# LED_Monitor_2.net
KiCad netlist of a schematic drawn in Altium Designer
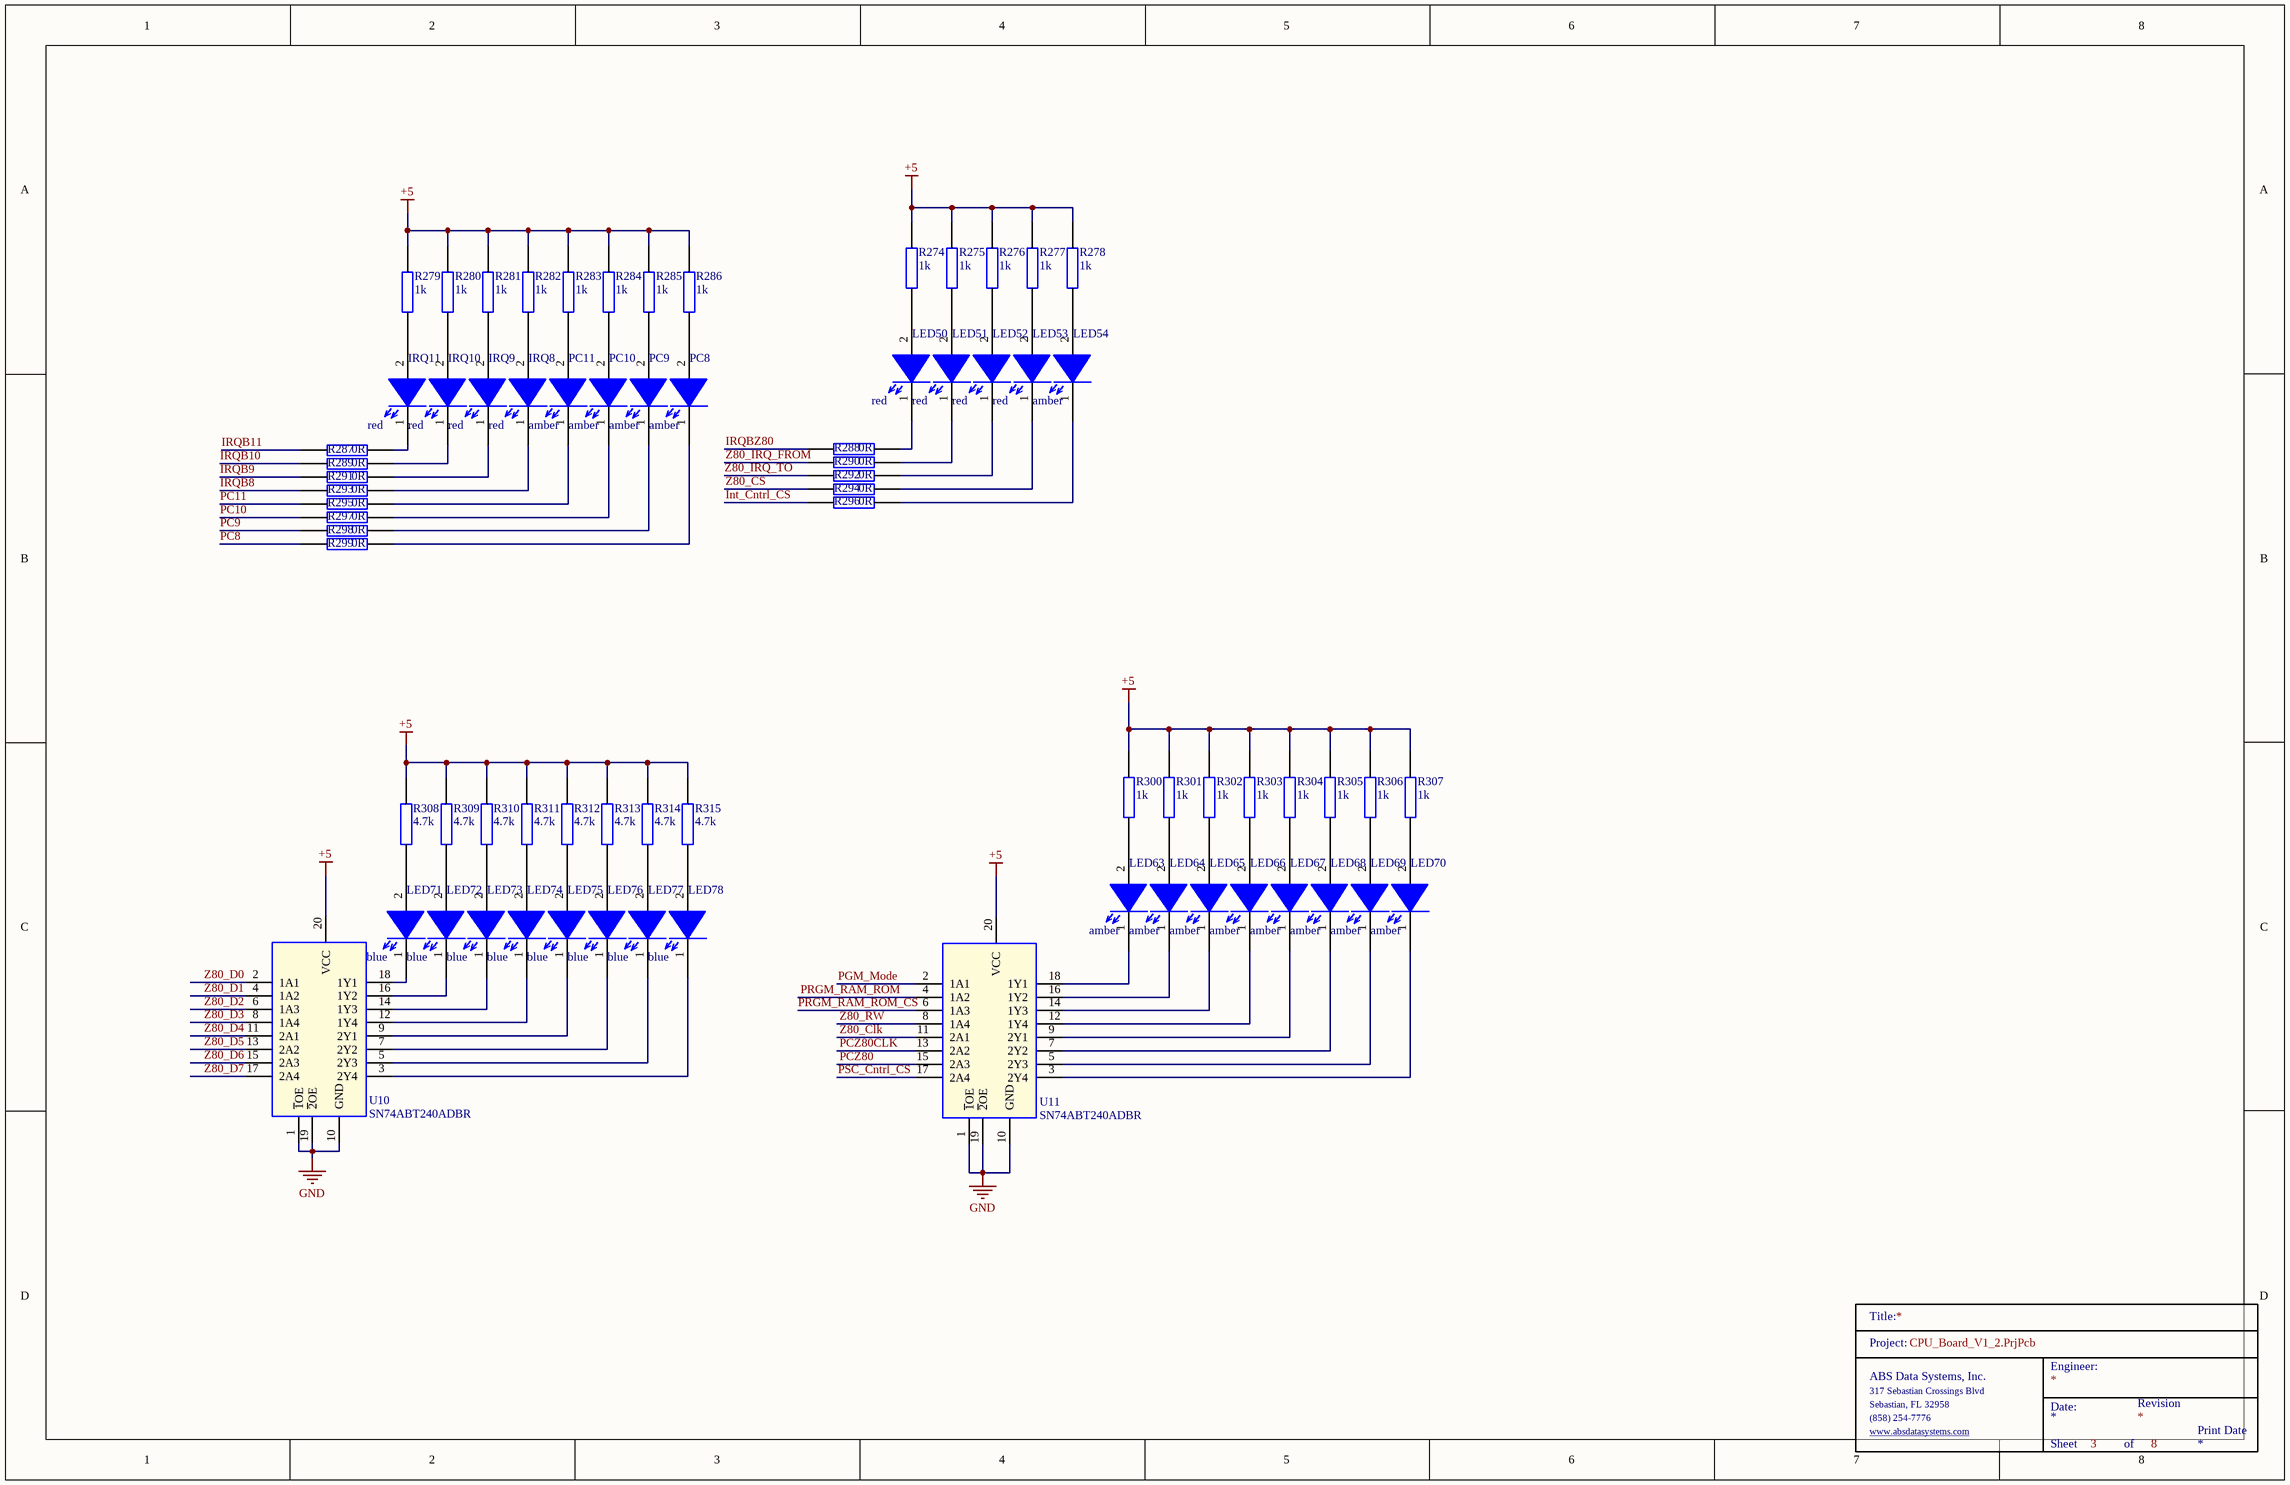
[diagram p0: LED_Monitor_2.SchDoc]

(export (version "E")
  (design (tool "Eeschema 10.0.6"))
  (components
    (comp (ref "IRQ8")
      (value "red")
      (footprint "0603_Diode")
      (description "Wurth Elektronik 0603 red")
      (fields
        (field (name "MANUFACTURER") "Wurth Electronics")
        (field (name "MANUFACTURER PART NUMBER") "150060GS75000")
      )
      (libsource (lib "Misc") (part "150060RS75000"))
    )
    (comp (ref "IRQ9")
      (value "red")
      (footprint "0603_Diode")
      (description "Wurth Elektronik 0603 red")
      (fields
        (field (name "MANUFACTURER") "Wurth Electronics")
        (field (name "MANUFACTURER PART NUMBER") "150060GS75000")
      )
      (libsource (lib "Misc") (part "150060RS75000"))
    )
    (comp (ref "IRQ10")
      (value "red")
      (footprint "0603_Diode")
      (description "Wurth Elektronik 0603 red")
      (fields
        (field (name "MANUFACTURER") "Wurth Electronics")
        (field (name "MANUFACTURER PART NUMBER") "150060GS75000")
      )
      (libsource (lib "Misc") (part "150060RS75000"))
    )
    (comp (ref "IRQ11")
      (value "red")
      (footprint "0603_Diode")
      (description "Wurth Elektronik 0603 red")
      (fields
        (field (name "MANUFACTURER") "Wurth Electronics")
        (field (name "MANUFACTURER PART NUMBER") "150060GS75000")
      )
      (libsource (lib "Misc") (part "150060RS75000"))
    )
    (comp (ref "LED50")
      (value "red")
      (footprint "0603_Diode")
      (description "Wurth Elektronik 0603 red")
      (fields
        (field (name "MANUFACTURER") "Wurth Electronics")
        (field (name "MANUFACTURER PART NUMBER") "150060GS75000")
      )
      (libsource (lib "Misc") (part "150060RS75000"))
    )
    (comp (ref "LED51")
      (value "red")
      (footprint "0603_Diode")
      (description "Wurth Elektronik 0603 red")
      (fields
        (field (name "MANUFACTURER") "Wurth Electronics")
        (field (name "MANUFACTURER PART NUMBER") "150060GS75000")
      )
      (libsource (lib "Misc") (part "150060RS75000"))
    )
    (comp (ref "LED52")
      (value "red")
      (footprint "0603_Diode")
      (description "Wurth Elektronik 0603 red")
      (fields
        (field (name "MANUFACTURER") "Wurth Electronics")
        (field (name "MANUFACTURER PART NUMBER") "150060GS75000")
      )
      (libsource (lib "Misc") (part "150060RS75000"))
    )
    (comp (ref "LED53")
      (value "red")
      (footprint "0603_Diode")
      (description "Wurth Elektronik 0603 red")
      (fields
        (field (name "MANUFACTURER") "Wurth Electronics")
        (field (name "MANUFACTURER PART NUMBER") "150060GS75000")
      )
      (libsource (lib "Misc") (part "150060RS75000"))
    )
    (comp (ref "LED54")
      (value "amber")
      (footprint "0603_Diode")
      (description "Wurth Elektronik 0603 amber")
      (fields
        (field (name "MANUFACTURER") "Wurth Electronics")
        (field (name "MANUFACTURER PART NUMBER") "150060GS75000")
      )
      (libsource (lib "Misc") (part "150060AS75000"))
    )
    (comp (ref "LED63")
      (value "amber")
      (footprint "0603_Diode")
      (description "Wurth Elektronik 0603 amber")
      (fields
        (field (name "MANUFACTURER") "Wurth Electronics")
        (field (name "MANUFACTURER PART NUMBER") "150060GS75000")
      )
      (libsource (lib "Misc") (part "150060AS75000"))
    )
    (comp (ref "LED64")
      (value "amber")
      (footprint "0603_Diode")
      (description "Wurth Elektronik 0603 amber")
      (fields
        (field (name "MANUFACTURER") "Wurth Electronics")
        (field (name "MANUFACTURER PART NUMBER") "150060GS75000")
      )
      (libsource (lib "Misc") (part "150060AS75000"))
    )
    (comp (ref "LED65")
      (value "amber")
      (footprint "0603_Diode")
      (description "Wurth Elektronik 0603 amber")
      (fields
        (field (name "MANUFACTURER") "Wurth Electronics")
        (field (name "MANUFACTURER PART NUMBER") "150060GS75000")
      )
      (libsource (lib "Misc") (part "150060AS75000"))
    )
    (comp (ref "LED66")
      (value "amber")
      (footprint "0603_Diode")
      (description "Wurth Elektronik 0603 amber")
      (fields
        (field (name "MANUFACTURER") "Wurth Electronics")
        (field (name "MANUFACTURER PART NUMBER") "150060GS75000")
      )
      (libsource (lib "Misc") (part "150060AS75000"))
    )
    (comp (ref "LED67")
      (value "amber")
      (footprint "0603_Diode")
      (description "Wurth Elektronik 0603 amber")
      (fields
        (field (name "MANUFACTURER") "Wurth Electronics")
        (field (name "MANUFACTURER PART NUMBER") "150060GS75000")
      )
      (libsource (lib "Misc") (part "150060AS75000"))
    )
    (comp (ref "LED68")
      (value "amber")
      (footprint "0603_Diode")
      (description "Wurth Elektronik 0603 amber")
      (fields
        (field (name "MANUFACTURER") "Wurth Electronics")
        (field (name "MANUFACTURER PART NUMBER") "150060GS75000")
      )
      (libsource (lib "Misc") (part "150060AS75000"))
    )
    (comp (ref "LED69")
      (value "amber")
      (footprint "0603_Diode")
      (description "Wurth Elektronik 0603 amber")
      (fields
        (field (name "MANUFACTURER") "Wurth Electronics")
        (field (name "MANUFACTURER PART NUMBER") "150060GS75000")
      )
      (libsource (lib "Misc") (part "150060AS75000"))
    )
    (comp (ref "LED70")
      (value "amber")
      (footprint "0603_Diode")
      (description "Wurth Elektronik 0603 amber")
      (fields
        (field (name "MANUFACTURER") "Wurth Electronics")
        (field (name "MANUFACTURER PART NUMBER") "150060GS75000")
      )
      (libsource (lib "Misc") (part "150060AS75000"))
    )
    (comp (ref "LED71")
      (value "blue")
      (footprint "0603_Diode")
      (description "Wurth Elektronik 0603 blue")
      (fields
        (field (name "MANUFACTURER") "Wurth Electronics")
        (field (name "MANUFACTURER PART NUMBER") "150060GS75000")
      )
      (libsource (lib "Misc") (part "150060BS75000"))
    )
    (comp (ref "LED72")
      (value "blue")
      (footprint "0603_Diode")
      (description "Wurth Elektronik 0603 blue")
      (fields
        (field (name "MANUFACTURER") "Wurth Electronics")
        (field (name "MANUFACTURER PART NUMBER") "150060GS75000")
      )
      (libsource (lib "Misc") (part "150060BS75000"))
    )
    (comp (ref "LED73")
      (value "blue")
      (footprint "0603_Diode")
      (description "Wurth Elektronik 0603 blue")
      (fields
        (field (name "MANUFACTURER") "Wurth Electronics")
        (field (name "MANUFACTURER PART NUMBER") "150060GS75000")
      )
      (libsource (lib "Misc") (part "150060BS75000"))
    )
    (comp (ref "LED74")
      (value "blue")
      (footprint "0603_Diode")
      (description "Wurth Elektronik 0603 blue")
      (fields
        (field (name "MANUFACTURER") "Wurth Electronics")
        (field (name "MANUFACTURER PART NUMBER") "150060GS75000")
      )
      (libsource (lib "Misc") (part "150060BS75000"))
    )
    (comp (ref "LED75")
      (value "blue")
      (footprint "0603_Diode")
      (description "Wurth Elektronik 0603 blue")
      (fields
        (field (name "MANUFACTURER") "Wurth Electronics")
        (field (name "MANUFACTURER PART NUMBER") "150060GS75000")
      )
      (libsource (lib "Misc") (part "150060BS75000"))
    )
    (comp (ref "LED76")
      (value "blue")
      (footprint "0603_Diode")
      (description "Wurth Elektronik 0603 blue")
      (fields
        (field (name "MANUFACTURER") "Wurth Electronics")
        (field (name "MANUFACTURER PART NUMBER") "150060GS75000")
      )
      (libsource (lib "Misc") (part "150060BS75000"))
    )
    (comp (ref "LED77")
      (value "blue")
      (footprint "0603_Diode")
      (description "Wurth Elektronik 0603 blue")
      (fields
        (field (name "MANUFACTURER") "Wurth Electronics")
        (field (name "MANUFACTURER PART NUMBER") "150060GS75000")
      )
      (libsource (lib "Misc") (part "150060BS75000"))
    )
    (comp (ref "LED78")
      (value "blue")
      (footprint "0603_Diode")
      (description "Wurth Elektronik 0603 blue")
      (fields
        (field (name "MANUFACTURER") "Wurth Electronics")
        (field (name "MANUFACTURER PART NUMBER") "150060GS75000")
      )
      (libsource (lib "Misc") (part "150060BS75000"))
    )
    (comp (ref "PC8")
      (value "amber")
      (footprint "0603_Diode")
      (description "Wurth Elektronik 0603 amber")
      (fields
        (field (name "MANUFACTURER") "Wurth Electronics")
        (field (name "MANUFACTURER PART NUMBER") "150060GS75000")
      )
      (libsource (lib "Misc") (part "150060AS75000"))
    )
    (comp (ref "PC9")
      (value "amber")
      (footprint "0603_Diode")
      (description "Wurth Elektronik 0603 amber")
      (fields
        (field (name "MANUFACTURER") "Wurth Electronics")
        (field (name "MANUFACTURER PART NUMBER") "150060GS75000")
      )
      (libsource (lib "Misc") (part "150060AS75000"))
    )
    (comp (ref "PC10")
      (value "amber")
      (footprint "0603_Diode")
      (description "Wurth Elektronik 0603 amber")
      (fields
        (field (name "MANUFACTURER") "Wurth Electronics")
        (field (name "MANUFACTURER PART NUMBER") "150060GS75000")
      )
      (libsource (lib "Misc") (part "150060AS75000"))
    )
    (comp (ref "PC11")
      (value "amber")
      (footprint "0603_Diode")
      (description "Wurth Elektronik 0603 amber")
      (fields
        (field (name "MANUFACTURER") "Wurth Electronics")
        (field (name "MANUFACTURER PART NUMBER") "150060GS75000")
      )
      (libsource (lib "Misc") (part "150060AS75000"))
    )
    (comp (ref "R274")
      (value "1k")
      (footprint "0603")
      (description "YAGEO 0603 1k ohm")
      (fields
        (field (name "MOUSER PART NUMBER") "603-RC0603JR-070RL")
        (field (name "MANUFACTURER_PART_NUMBER") "RC0603JR-070RL")
      )
      (libsource (lib "Resistors") (part "AC0603FR-7W1KL_1"))
    )
    (comp (ref "R275")
      (value "1k")
      (footprint "0603")
      (description "YAGEO 0603 1k ohm")
      (fields
        (field (name "MOUSER PART NUMBER") "603-RC0603JR-070RL")
        (field (name "MANUFACTURER_PART_NUMBER") "RC0603JR-070RL")
      )
      (libsource (lib "Resistors") (part "AC0603FR-7W1KL_1"))
    )
    (comp (ref "R276")
      (value "1k")
      (footprint "0603")
      (description "YAGEO 0603 1k ohm")
      (fields
        (field (name "MOUSER PART NUMBER") "603-RC0603JR-070RL")
        (field (name "MANUFACTURER_PART_NUMBER") "RC0603JR-070RL")
      )
      (libsource (lib "Resistors") (part "AC0603FR-7W1KL_1"))
    )
    (comp (ref "R277")
      (value "1k")
      (footprint "0603")
      (description "YAGEO 0603 1k ohm")
      (fields
        (field (name "MOUSER PART NUMBER") "603-RC0603JR-070RL")
        (field (name "MANUFACTURER_PART_NUMBER") "RC0603JR-070RL")
      )
      (libsource (lib "Resistors") (part "AC0603FR-7W1KL_1"))
    )
    (comp (ref "R278")
      (value "1k")
      (footprint "0603")
      (description "YAGEO 0603 1k ohm")
      (fields
        (field (name "MOUSER PART NUMBER") "603-RC0603JR-070RL")
        (field (name "MANUFACTURER_PART_NUMBER") "RC0603JR-070RL")
      )
      (libsource (lib "Resistors") (part "AC0603FR-7W1KL_1"))
    )
    (comp (ref "R279")
      (value "1k")
      (footprint "0603")
      (description "YAGEO 0603 1k ohm")
      (fields
        (field (name "MOUSER PART NUMBER") "603-RC0603JR-070RL")
        (field (name "MANUFACTURER_PART_NUMBER") "RC0603JR-070RL")
      )
      (libsource (lib "Resistors") (part "AC0603FR-7W1KL_1"))
    )
    (comp (ref "R280")
      (value "1k")
      (footprint "0603")
      (description "YAGEO 0603 1k ohm")
      (fields
        (field (name "MOUSER PART NUMBER") "603-RC0603JR-070RL")
        (field (name "MANUFACTURER_PART_NUMBER") "RC0603JR-070RL")
      )
      (libsource (lib "Resistors") (part "AC0603FR-7W1KL_1"))
    )
    (comp (ref "R281")
      (value "1k")
      (footprint "0603")
      (description "YAGEO 0603 1k ohm")
      (fields
        (field (name "MOUSER PART NUMBER") "603-RC0603JR-070RL")
        (field (name "MANUFACTURER_PART_NUMBER") "RC0603JR-070RL")
      )
      (libsource (lib "Resistors") (part "AC0603FR-7W1KL_1"))
    )
    (comp (ref "R282")
      (value "1k")
      (footprint "0603")
      (description "YAGEO 0603 1k ohm")
      (fields
        (field (name "MOUSER PART NUMBER") "603-RC0603JR-070RL")
        (field (name "MANUFACTURER_PART_NUMBER") "RC0603JR-070RL")
      )
      (libsource (lib "Resistors") (part "AC0603FR-7W1KL_1"))
    )
    (comp (ref "R283")
      (value "1k")
      (footprint "0603")
      (description "YAGEO 0603 1k ohm")
      (fields
        (field (name "MOUSER PART NUMBER") "603-RC0603JR-070RL")
        (field (name "MANUFACTURER_PART_NUMBER") "RC0603JR-070RL")
      )
      (libsource (lib "Resistors") (part "AC0603FR-7W1KL_1"))
    )
    (comp (ref "R284")
      (value "1k")
      (footprint "0603")
      (description "YAGEO 0603 1k ohm")
      (fields
        (field (name "MOUSER PART NUMBER") "603-RC0603JR-070RL")
        (field (name "MANUFACTURER_PART_NUMBER") "RC0603JR-070RL")
      )
      (libsource (lib "Resistors") (part "AC0603FR-7W1KL_1"))
    )
    (comp (ref "R285")
      (value "1k")
      (footprint "0603")
      (description "YAGEO 0603 1k ohm")
      (fields
        (field (name "MOUSER PART NUMBER") "603-RC0603JR-070RL")
        (field (name "MANUFACTURER_PART_NUMBER") "RC0603JR-070RL")
      )
      (libsource (lib "Resistors") (part "AC0603FR-7W1KL_1"))
    )
    (comp (ref "R286")
      (value "1k")
      (footprint "0603")
      (description "YAGEO 0603 1k ohm")
      (fields
        (field (name "MOUSER PART NUMBER") "603-RC0603JR-070RL")
        (field (name "MANUFACTURER_PART_NUMBER") "RC0603JR-070RL")
      )
      (libsource (lib "Resistors") (part "AC0603FR-7W1KL_1"))
    )
    (comp (ref "R287")
      (value "0R")
      (footprint "0603")
      (description "YAGEO 0603 0 ohm")
      (fields
        (field (name "MOUSER PART NUMBER") "603-RC0603JR-070RL")
        (field (name "MANUFACTURER_PART_NUMBER") "RC0603JR-070RL")
      )
      (libsource (lib "Resistors") (part "RC0603JR-070RL"))
    )
    (comp (ref "R288")
      (value "0R")
      (footprint "0603")
      (description "YAGEO 0603 0 ohm")
      (fields
        (field (name "MOUSER PART NUMBER") "603-RC0603JR-070RL")
        (field (name "MANUFACTURER_PART_NUMBER") "RC0603JR-070RL")
      )
      (libsource (lib "Resistors") (part "RC0603JR-070RL"))
    )
    (comp (ref "R289")
      (value "0R")
      (footprint "0603")
      (description "YAGEO 0603 0 ohm")
      (fields
        (field (name "MOUSER PART NUMBER") "603-RC0603JR-070RL")
        (field (name "MANUFACTURER_PART_NUMBER") "RC0603JR-070RL")
      )
      (libsource (lib "Resistors") (part "RC0603JR-070RL"))
    )
    (comp (ref "R290")
      (value "0R")
      (footprint "0603")
      (description "YAGEO 0603 0 ohm")
      (fields
        (field (name "MOUSER PART NUMBER") "603-RC0603JR-070RL")
        (field (name "MANUFACTURER_PART_NUMBER") "RC0603JR-070RL")
      )
      (libsource (lib "Resistors") (part "RC0603JR-070RL"))
    )
    (comp (ref "R291")
      (value "0R")
      (footprint "0603")
      (description "YAGEO 0603 0 ohm")
      (fields
        (field (name "MOUSER PART NUMBER") "603-RC0603JR-070RL")
        (field (name "MANUFACTURER_PART_NUMBER") "RC0603JR-070RL")
      )
      (libsource (lib "Resistors") (part "RC0603JR-070RL"))
    )
    (comp (ref "R292")
      (value "0R")
      (footprint "0603")
      (description "YAGEO 0603 0 ohm")
      (fields
        (field (name "MOUSER PART NUMBER") "603-RC0603JR-070RL")
        (field (name "MANUFACTURER_PART_NUMBER") "RC0603JR-070RL")
      )
      (libsource (lib "Resistors") (part "RC0603JR-070RL"))
    )
    (comp (ref "R293")
      (value "0R")
      (footprint "0603")
      (description "YAGEO 0603 0 ohm")
      (fields
        (field (name "MOUSER PART NUMBER") "603-RC0603JR-070RL")
        (field (name "MANUFACTURER_PART_NUMBER") "RC0603JR-070RL")
      )
      (libsource (lib "Resistors") (part "RC0603JR-070RL"))
    )
    (comp (ref "R294")
      (value "0R")
      (footprint "0603")
      (description "YAGEO 0603 0 ohm")
      (fields
        (field (name "MOUSER PART NUMBER") "603-RC0603JR-070RL")
        (field (name "MANUFACTURER_PART_NUMBER") "RC0603JR-070RL")
      )
      (libsource (lib "Resistors") (part "RC0603JR-070RL"))
    )
    (comp (ref "R295")
      (value "0R")
      (footprint "0603")
      (description "YAGEO 0603 0 ohm")
      (fields
        (field (name "MOUSER PART NUMBER") "603-RC0603JR-070RL")
        (field (name "MANUFACTURER_PART_NUMBER") "RC0603JR-070RL")
      )
      (libsource (lib "Resistors") (part "RC0603JR-070RL"))
    )
    (comp (ref "R296")
      (value "0R")
      (footprint "0603")
      (description "YAGEO 0603 0 ohm")
      (fields
        (field (name "MOUSER PART NUMBER") "603-RC0603JR-070RL")
        (field (name "MANUFACTURER_PART_NUMBER") "RC0603JR-070RL")
      )
      (libsource (lib "Resistors") (part "RC0603JR-070RL"))
    )
    (comp (ref "R297")
      (value "0R")
      (footprint "0603")
      (description "YAGEO 0603 0 ohm")
      (fields
        (field (name "MOUSER PART NUMBER") "603-RC0603JR-070RL")
        (field (name "MANUFACTURER_PART_NUMBER") "RC0603JR-070RL")
      )
      (libsource (lib "Resistors") (part "RC0603JR-070RL"))
    )
    (comp (ref "R298")
      (value "0R")
      (footprint "0603")
      (description "YAGEO 0603 0 ohm")
      (fields
        (field (name "MOUSER PART NUMBER") "603-RC0603JR-070RL")
        (field (name "MANUFACTURER_PART_NUMBER") "RC0603JR-070RL")
      )
      (libsource (lib "Resistors") (part "RC0603JR-070RL"))
    )
    (comp (ref "R299")
      (value "0R")
      (footprint "0603")
      (description "YAGEO 0603 0 ohm")
      (fields
        (field (name "MOUSER PART NUMBER") "603-RC0603JR-070RL")
        (field (name "MANUFACTURER_PART_NUMBER") "RC0603JR-070RL")
      )
      (libsource (lib "Resistors") (part "RC0603JR-070RL"))
    )
    (comp (ref "R300")
      (value "1k")
      (footprint "0603")
      (description "YAGEO 0603 1k ohm")
      (fields
        (field (name "MOUSER PART NUMBER") "603-RC0603JR-070RL")
        (field (name "MANUFACTURER_PART_NUMBER") "RC0603JR-070RL")
      )
      (libsource (lib "Resistors") (part "AC0603FR-7W1KL_1"))
    )
    (comp (ref "R301")
      (value "1k")
      (footprint "0603")
      (description "YAGEO 0603 1k ohm")
      (fields
        (field (name "MOUSER PART NUMBER") "603-RC0603JR-070RL")
        (field (name "MANUFACTURER_PART_NUMBER") "RC0603JR-070RL")
      )
      (libsource (lib "Resistors") (part "AC0603FR-7W1KL_1"))
    )
    (comp (ref "R302")
      (value "1k")
      (footprint "0603")
      (description "YAGEO 0603 1k ohm")
      (fields
        (field (name "MOUSER PART NUMBER") "603-RC0603JR-070RL")
        (field (name "MANUFACTURER_PART_NUMBER") "RC0603JR-070RL")
      )
      (libsource (lib "Resistors") (part "AC0603FR-7W1KL_1"))
    )
    (comp (ref "R303")
      (value "1k")
      (footprint "0603")
      (description "YAGEO 0603 1k ohm")
      (fields
        (field (name "MOUSER PART NUMBER") "603-RC0603JR-070RL")
        (field (name "MANUFACTURER_PART_NUMBER") "RC0603JR-070RL")
      )
      (libsource (lib "Resistors") (part "AC0603FR-7W1KL_1"))
    )
    (comp (ref "R304")
      (value "1k")
      (footprint "0603")
      (description "YAGEO 0603 1k ohm")
      (fields
        (field (name "MOUSER PART NUMBER") "603-RC0603JR-070RL")
        (field (name "MANUFACTURER_PART_NUMBER") "RC0603JR-070RL")
      )
      (libsource (lib "Resistors") (part "AC0603FR-7W1KL_1"))
    )
    (comp (ref "R305")
      (value "1k")
      (footprint "0603")
      (description "YAGEO 0603 1k ohm")
      (fields
        (field (name "MOUSER PART NUMBER") "603-RC0603JR-070RL")
        (field (name "MANUFACTURER_PART_NUMBER") "RC0603JR-070RL")
      )
      (libsource (lib "Resistors") (part "AC0603FR-7W1KL_1"))
    )
    (comp (ref "R306")
      (value "1k")
      (footprint "0603")
      (description "YAGEO 0603 1k ohm")
      (fields
        (field (name "MOUSER PART NUMBER") "603-RC0603JR-070RL")
        (field (name "MANUFACTURER_PART_NUMBER") "RC0603JR-070RL")
      )
      (libsource (lib "Resistors") (part "AC0603FR-7W1KL_1"))
    )
    (comp (ref "R307")
      (value "1k")
      (footprint "0603")
      (description "YAGEO 0603 1k ohm")
      (fields
        (field (name "MOUSER PART NUMBER") "603-RC0603JR-070RL")
        (field (name "MANUFACTURER_PART_NUMBER") "RC0603JR-070RL")
      )
      (libsource (lib "Resistors") (part "AC0603FR-7W1KL_1"))
    )
    (comp (ref "R308")
      (value "4.7k")
      (footprint "0603")
      (description "YAGEO 0603 4.7k")
      (fields
        (field (name "MOUSER PART NUMBER") "603-RC0603JR-070RL")
        (field (name "MANUFACTURER_PART_NUMBER") "RC0603JR-070RL")
      )
      (libsource (lib "Resistors") (part "RC0603FR-104K7L"))
    )
    (comp (ref "R309")
      (value "4.7k")
      (footprint "0603")
      (description "YAGEO 0603 4.7k")
      (fields
        (field (name "MOUSER PART NUMBER") "603-RC0603JR-070RL")
        (field (name "MANUFACTURER_PART_NUMBER") "RC0603JR-070RL")
      )
      (libsource (lib "Resistors") (part "RC0603FR-104K7L"))
    )
    (comp (ref "R310")
      (value "4.7k")
      (footprint "0603")
      (description "YAGEO 0603 4.7k")
      (fields
        (field (name "MOUSER PART NUMBER") "603-RC0603JR-070RL")
        (field (name "MANUFACTURER_PART_NUMBER") "RC0603JR-070RL")
      )
      (libsource (lib "Resistors") (part "RC0603FR-104K7L"))
    )
    (comp (ref "R311")
      (value "4.7k")
      (footprint "0603")
      (description "YAGEO 0603 4.7k")
      (fields
        (field (name "MOUSER PART NUMBER") "603-RC0603JR-070RL")
        (field (name "MANUFACTURER_PART_NUMBER") "RC0603JR-070RL")
      )
      (libsource (lib "Resistors") (part "RC0603FR-104K7L"))
    )
    (comp (ref "R312")
      (value "4.7k")
      (footprint "0603")
      (description "YAGEO 0603 4.7k")
      (fields
        (field (name "MOUSER PART NUMBER") "603-RC0603JR-070RL")
        (field (name "MANUFACTURER_PART_NUMBER") "RC0603JR-070RL")
      )
      (libsource (lib "Resistors") (part "RC0603FR-104K7L"))
    )
    (comp (ref "R313")
      (value "4.7k")
      (footprint "0603")
      (description "YAGEO 0603 4.7k")
      (fields
        (field (name "MOUSER PART NUMBER") "603-RC0603JR-070RL")
        (field (name "MANUFACTURER_PART_NUMBER") "RC0603JR-070RL")
      )
      (libsource (lib "Resistors") (part "RC0603FR-104K7L"))
    )
    (comp (ref "R314")
      (value "4.7k")
      (footprint "0603")
      (description "YAGEO 0603 4.7k")
      (fields
        (field (name "MOUSER PART NUMBER") "603-RC0603JR-070RL")
        (field (name "MANUFACTURER_PART_NUMBER") "RC0603JR-070RL")
      )
      (libsource (lib "Resistors") (part "RC0603FR-104K7L"))
    )
    (comp (ref "R315")
      (value "4.7k")
      (footprint "0603")
      (description "YAGEO 0603 4.7k")
      (fields
        (field (name "MOUSER PART NUMBER") "603-RC0603JR-070RL")
        (field (name "MANUFACTURER_PART_NUMBER") "RC0603JR-070RL")
      )
      (libsource (lib "Resistors") (part "RC0603FR-104K7L"))
    )
    (comp (ref "U10")
      (value "SN74ABT240ADBR")
      (footprint "SOP65P780X200-20N")
      (description "Octal Buffers/Drivers With 3-State Outputs")
      (fields (field (name "MOUSER PART NUMBER") "595-SN74ABT240ADBR"))
      (libsource (lib "Logic") (part "SN74ABT240ADBR"))
    )
    (comp (ref "U11")
      (value "SN74ABT240ADBR")
      (footprint "SOP65P780X200-20N")
      (description "Octal Buffers/Drivers With 3-State Outputs")
      (fields (field (name "MOUSER PART NUMBER") "595-SN74ABT240ADBR"))
      (libsource (lib "Logic") (part "SN74ABT240ADBR"))
    )
  )
  (nets
    (net (code "1") (name "+5") (class "Default")
      (node (ref "R274") (pin "1") (pinfunction "1_1") (pintype "passive"))
      (node (ref "R275") (pin "1") (pinfunction "1_1") (pintype "passive"))
      (node (ref "R276") (pin "1") (pinfunction "1_1") (pintype "passive"))
      (node (ref "R277") (pin "1") (pinfunction "1_1") (pintype "passive"))
      (node (ref "R278") (pin "1") (pinfunction "1_1") (pintype "passive"))
      (node (ref "R279") (pin "1") (pinfunction "1_1") (pintype "passive"))
      (node (ref "R280") (pin "1") (pinfunction "1_1") (pintype "passive"))
      (node (ref "R281") (pin "1") (pinfunction "1_1") (pintype "passive"))
      (node (ref "R282") (pin "1") (pinfunction "1_1") (pintype "passive"))
      (node (ref "R283") (pin "1") (pinfunction "1_1") (pintype "passive"))
      (node (ref "R284") (pin "1") (pinfunction "1_1") (pintype "passive"))
      (node (ref "R285") (pin "1") (pinfunction "1_1") (pintype "passive"))
      (node (ref "R286") (pin "1") (pinfunction "1_1") (pintype "passive"))
      (node (ref "R300") (pin "1") (pinfunction "1_1") (pintype "passive"))
      (node (ref "R301") (pin "1") (pinfunction "1_1") (pintype "passive"))
      (node (ref "R302") (pin "1") (pinfunction "1_1") (pintype "passive"))
      (node (ref "R303") (pin "1") (pinfunction "1_1") (pintype "passive"))
      (node (ref "R304") (pin "1") (pinfunction "1_1") (pintype "passive"))
      (node (ref "R305") (pin "1") (pinfunction "1_1") (pintype "passive"))
      (node (ref "R306") (pin "1") (pinfunction "1_1") (pintype "passive"))
      (node (ref "R307") (pin "1") (pinfunction "1_1") (pintype "passive"))
      (node (ref "R308") (pin "1") (pinfunction "1_1") (pintype "passive"))
      (node (ref "R309") (pin "1") (pinfunction "1_1") (pintype "passive"))
      (node (ref "R310") (pin "1") (pinfunction "1_1") (pintype "passive"))
      (node (ref "R311") (pin "1") (pinfunction "1_1") (pintype "passive"))
      (node (ref "R312") (pin "1") (pinfunction "1_1") (pintype "passive"))
      (node (ref "R313") (pin "1") (pinfunction "1_1") (pintype "passive"))
      (node (ref "R314") (pin "1") (pinfunction "1_1") (pintype "passive"))
      (node (ref "R315") (pin "1") (pinfunction "1_1") (pintype "passive"))
      (node (ref "U10") (pin "20") (pinfunction "VCC_20") (pintype "passive"))
      (node (ref "U11") (pin "20") (pinfunction "VCC_20") (pintype "passive"))
    )
    (net (code "2") (name "/IRQB8") (class "Default")
      (node (ref "R293") (pin "1") (pinfunction "1_1") (pintype "passive"))
    )
    (net (code "3") (name "/IRQB9") (class "Default")
      (node (ref "R291") (pin "1") (pinfunction "1_1") (pintype "passive"))
    )
    (net (code "4") (name "/IRQB10") (class "Default")
      (node (ref "R289") (pin "1") (pinfunction "1_1") (pintype "passive"))
    )
    (net (code "5") (name "/IRQB11") (class "Default")
      (node (ref "R287") (pin "1") (pinfunction "1_1") (pintype "passive"))
    )
    (net (code "6") (name "/IRQBZ80") (class "Default")
      (node (ref "R288") (pin "1") (pinfunction "1_1") (pintype "passive"))
    )
    (net (code "7") (name "/Int_Cntrl_CS") (class "Default")
      (node (ref "R296") (pin "1") (pinfunction "1_1") (pintype "passive"))
    )
    (net (code "8") (name "/PC8") (class "Default")
      (node (ref "R299") (pin "1") (pinfunction "1_1") (pintype "passive"))
    )
    (net (code "9") (name "/PC9") (class "Default")
      (node (ref "R298") (pin "1") (pinfunction "1_1") (pintype "passive"))
    )
    (net (code "10") (name "/PC10") (class "Default")
      (node (ref "R297") (pin "1") (pinfunction "1_1") (pintype "passive"))
    )
    (net (code "11") (name "/PC11") (class "Default")
      (node (ref "R295") (pin "1") (pinfunction "1_1") (pintype "passive"))
    )
    (net (code "12") (name "/PCZ80") (class "Default")
      (node (ref "U11") (pin "15") (pinfunction "2A3_15") (pintype "passive"))
    )
    (net (code "13") (name "/PCZ80CLK") (class "Default")
      (node (ref "U11") (pin "13") (pinfunction "2A2_13") (pintype "passive"))
    )
    (net (code "14") (name "/PGM_Mode") (class "Default")
      (node (ref "U11") (pin "2") (pinfunction "1A1_2") (pintype "passive"))
    )
    (net (code "15") (name "/PRGM_RAM_ROM") (class "Default")
      (node (ref "U11") (pin "4") (pinfunction "1A2_4") (pintype "passive"))
    )
    (net (code "16") (name "/PRGM_RAM_ROM_CS") (class "Default")
      (node (ref "U11") (pin "6") (pinfunction "1A3_6") (pintype "passive"))
    )
    (net (code "17") (name "/PSC_Cntrl_CS") (class "Default")
      (node (ref "U11") (pin "17") (pinfunction "2A4_17") (pintype "passive"))
    )
    (net (code "18") (name "/Z80_CS") (class "Default")
      (node (ref "R294") (pin "1") (pinfunction "1_1") (pintype "passive"))
    )
    (net (code "19") (name "/Z80_Clk") (class "Default")
      (node (ref "U11") (pin "11") (pinfunction "2A1_11") (pintype "passive"))
    )
    (net (code "20") (name "/Z80_D0") (class "Default")
      (node (ref "U10") (pin "2") (pinfunction "1A1_2") (pintype "passive"))
    )
    (net (code "21") (name "/Z80_D1") (class "Default")
      (node (ref "U10") (pin "4") (pinfunction "1A2_4") (pintype "passive"))
    )
    (net (code "22") (name "/Z80_D2") (class "Default")
      (node (ref "U10") (pin "6") (pinfunction "1A3_6") (pintype "passive"))
    )
    (net (code "23") (name "/Z80_D3") (class "Default")
      (node (ref "U10") (pin "8") (pinfunction "1A4_8") (pintype "passive"))
    )
    (net (code "24") (name "/Z80_D4") (class "Default")
      (node (ref "U10") (pin "11") (pinfunction "2A1_11") (pintype "passive"))
    )
    (net (code "25") (name "/Z80_D5") (class "Default")
      (node (ref "U10") (pin "13") (pinfunction "2A2_13") (pintype "passive"))
    )
    (net (code "26") (name "/Z80_D6") (class "Default")
      (node (ref "U10") (pin "15") (pinfunction "2A3_15") (pintype "passive"))
    )
    (net (code "27") (name "/Z80_D7") (class "Default")
      (node (ref "U10") (pin "17") (pinfunction "2A4_17") (pintype "passive"))
    )
    (net (code "28") (name "/Z80_IRQ_FROM") (class "Default")
      (node (ref "R290") (pin "1") (pinfunction "1_1") (pintype "passive"))
    )
    (net (code "29") (name "/Z80_IRQ_TO") (class "Default")
      (node (ref "R292") (pin "1") (pinfunction "1_1") (pintype "passive"))
    )
    (net (code "30") (name "/Z80_RW") (class "Default")
      (node (ref "U11") (pin "8") (pinfunction "1A4_8") (pintype "passive"))
    )
    (net (code "31") (name "GND") (class "Default")
      (node (ref "U10") (pin "1") (pinfunction "~{1}OE_1") (pintype "passive"))
      (node (ref "U10") (pin "10") (pinfunction "GND_10") (pintype "passive"))
      (node (ref "U10") (pin "19") (pinfunction "~{2}OE_19") (pintype "passive"))
      (node (ref "U11") (pin "1") (pinfunction "~{1}OE_1") (pintype "passive"))
      (node (ref "U11") (pin "10") (pinfunction "GND_10") (pintype "passive"))
      (node (ref "U11") (pin "19") (pinfunction "~{2}OE_19") (pintype "passive"))
    )
    (net (code "32") (name "Net-(IRQ8-A)") (class "Default")
      (node (ref "IRQ8") (pin "2") (pinfunction "A_2") (pintype "passive"))
      (node (ref "R282") (pin "2") (pinfunction "2_2") (pintype "passive"))
    )
    (net (code "33") (name "Net-(IRQ8-K)") (class "Default")
      (node (ref "IRQ8") (pin "1") (pinfunction "K_1") (pintype "passive"))
      (node (ref "R293") (pin "2") (pinfunction "2_2") (pintype "passive"))
    )
    (net (code "34") (name "Net-(IRQ9-A)") (class "Default")
      (node (ref "IRQ9") (pin "2") (pinfunction "A_2") (pintype "passive"))
      (node (ref "R281") (pin "2") (pinfunction "2_2") (pintype "passive"))
    )
    (net (code "35") (name "Net-(IRQ9-K)") (class "Default")
      (node (ref "IRQ9") (pin "1") (pinfunction "K_1") (pintype "passive"))
      (node (ref "R291") (pin "2") (pinfunction "2_2") (pintype "passive"))
    )
    (net (code "36") (name "Net-(IRQ10-A)") (class "Default")
      (node (ref "IRQ10") (pin "2") (pinfunction "A_2") (pintype "passive"))
      (node (ref "R280") (pin "2") (pinfunction "2_2") (pintype "passive"))
    )
    (net (code "37") (name "Net-(IRQ10-K)") (class "Default")
      (node (ref "IRQ10") (pin "1") (pinfunction "K_1") (pintype "passive"))
      (node (ref "R289") (pin "2") (pinfunction "2_2") (pintype "passive"))
    )
    (net (code "38") (name "Net-(IRQ11-A)") (class "Default")
      (node (ref "IRQ11") (pin "2") (pinfunction "A_2") (pintype "passive"))
      (node (ref "R279") (pin "2") (pinfunction "2_2") (pintype "passive"))
    )
    (net (code "39") (name "Net-(IRQ11-K)") (class "Default")
      (node (ref "IRQ11") (pin "1") (pinfunction "K_1") (pintype "passive"))
      (node (ref "R287") (pin "2") (pinfunction "2_2") (pintype "passive"))
    )
    (net (code "40") (name "Net-(LED50-A)") (class "Default")
      (node (ref "LED50") (pin "2") (pinfunction "A_2") (pintype "passive"))
      (node (ref "R274") (pin "2") (pinfunction "2_2") (pintype "passive"))
    )
    (net (code "41") (name "Net-(LED50-K)") (class "Default")
      (node (ref "LED50") (pin "1") (pinfunction "K_1") (pintype "passive"))
      (node (ref "R288") (pin "2") (pinfunction "2_2") (pintype "passive"))
    )
    (net (code "42") (name "Net-(LED51-A)") (class "Default")
      (node (ref "LED51") (pin "2") (pinfunction "A_2") (pintype "passive"))
      (node (ref "R275") (pin "2") (pinfunction "2_2") (pintype "passive"))
    )
    (net (code "43") (name "Net-(LED51-K)") (class "Default")
      (node (ref "LED51") (pin "1") (pinfunction "K_1") (pintype "passive"))
      (node (ref "R290") (pin "2") (pinfunction "2_2") (pintype "passive"))
    )
    (net (code "44") (name "Net-(LED52-A)") (class "Default")
      (node (ref "LED52") (pin "2") (pinfunction "A_2") (pintype "passive"))
      (node (ref "R276") (pin "2") (pinfunction "2_2") (pintype "passive"))
    )
    (net (code "45") (name "Net-(LED52-K)") (class "Default")
      (node (ref "LED52") (pin "1") (pinfunction "K_1") (pintype "passive"))
      (node (ref "R292") (pin "2") (pinfunction "2_2") (pintype "passive"))
    )
    (net (code "46") (name "Net-(LED53-A)") (class "Default")
      (node (ref "LED53") (pin "2") (pinfunction "A_2") (pintype "passive"))
      (node (ref "R277") (pin "2") (pinfunction "2_2") (pintype "passive"))
    )
    (net (code "47") (name "Net-(LED53-K)") (class "Default")
      (node (ref "LED53") (pin "1") (pinfunction "K_1") (pintype "passive"))
      (node (ref "R294") (pin "2") (pinfunction "2_2") (pintype "passive"))
    )
    (net (code "48") (name "Net-(LED54-A)") (class "Default")
      (node (ref "LED54") (pin "2") (pinfunction "A_2") (pintype "passive"))
      (node (ref "R278") (pin "2") (pinfunction "2_2") (pintype "passive"))
    )
    (net (code "49") (name "Net-(LED54-K)") (class "Default")
      (node (ref "LED54") (pin "1") (pinfunction "K_1") (pintype "passive"))
      (node (ref "R296") (pin "2") (pinfunction "2_2") (pintype "passive"))
    )
    (net (code "50") (name "Net-(LED63-A)") (class "Default")
      (node (ref "LED63") (pin "2") (pinfunction "A_2") (pintype "passive"))
      (node (ref "R300") (pin "2") (pinfunction "2_2") (pintype "passive"))
    )
    (net (code "51") (name "Net-(LED63-K)") (class "Default")
      (node (ref "LED63") (pin "1") (pinfunction "K_1") (pintype "passive"))
      (node (ref "U11") (pin "18") (pinfunction "1Y1_18") (pintype "passive"))
    )
    (net (code "52") (name "Net-(LED64-A)") (class "Default")
      (node (ref "LED64") (pin "2") (pinfunction "A_2") (pintype "passive"))
      (node (ref "R301") (pin "2") (pinfunction "2_2") (pintype "passive"))
    )
    (net (code "53") (name "Net-(LED64-K)") (class "Default")
      (node (ref "LED64") (pin "1") (pinfunction "K_1") (pintype "passive"))
      (node (ref "U11") (pin "16") (pinfunction "1Y2_16") (pintype "passive"))
    )
    (net (code "54") (name "Net-(LED65-A)") (class "Default")
      (node (ref "LED65") (pin "2") (pinfunction "A_2") (pintype "passive"))
      (node (ref "R302") (pin "2") (pinfunction "2_2") (pintype "passive"))
    )
    (net (code "55") (name "Net-(LED65-K)") (class "Default")
      (node (ref "LED65") (pin "1") (pinfunction "K_1") (pintype "passive"))
      (node (ref "U11") (pin "14") (pinfunction "1Y3_14") (pintype "passive"))
    )
    (net (code "56") (name "Net-(LED66-A)") (class "Default")
      (node (ref "LED66") (pin "2") (pinfunction "A_2") (pintype "passive"))
      (node (ref "R303") (pin "2") (pinfunction "2_2") (pintype "passive"))
    )
    (net (code "57") (name "Net-(LED66-K)") (class "Default")
      (node (ref "LED66") (pin "1") (pinfunction "K_1") (pintype "passive"))
      (node (ref "U11") (pin "12") (pinfunction "1Y4_12") (pintype "passive"))
    )
    (net (code "58") (name "Net-(LED67-A)") (class "Default")
      (node (ref "LED67") (pin "2") (pinfunction "A_2") (pintype "passive"))
      (node (ref "R304") (pin "2") (pinfunction "2_2") (pintype "passive"))
    )
    (net (code "59") (name "Net-(LED67-K)") (class "Default")
      (node (ref "LED67") (pin "1") (pinfunction "K_1") (pintype "passive"))
      (node (ref "U11") (pin "9") (pinfunction "2Y1_9") (pintype "passive"))
    )
    (net (code "60") (name "Net-(LED68-A)") (class "Default")
      (node (ref "LED68") (pin "2") (pinfunction "A_2") (pintype "passive"))
      (node (ref "R305") (pin "2") (pinfunction "2_2") (pintype "passive"))
    )
    (net (code "61") (name "Net-(LED68-K)") (class "Default")
      (node (ref "LED68") (pin "1") (pinfunction "K_1") (pintype "passive"))
      (node (ref "U11") (pin "7") (pinfunction "2Y2_7") (pintype "passive"))
    )
    (net (code "62") (name "Net-(LED69-A)") (class "Default")
      (node (ref "LED69") (pin "2") (pinfunction "A_2") (pintype "passive"))
      (node (ref "R306") (pin "2") (pinfunction "2_2") (pintype "passive"))
    )
    (net (code "63") (name "Net-(LED69-K)") (class "Default")
      (node (ref "LED69") (pin "1") (pinfunction "K_1") (pintype "passive"))
      (node (ref "U11") (pin "5") (pinfunction "2Y3_5") (pintype "passive"))
    )
    (net (code "64") (name "Net-(LED70-A)") (class "Default")
      (node (ref "LED70") (pin "2") (pinfunction "A_2") (pintype "passive"))
      (node (ref "R307") (pin "2") (pinfunction "2_2") (pintype "passive"))
    )
    (net (code "65") (name "Net-(LED70-K)") (class "Default")
      (node (ref "LED70") (pin "1") (pinfunction "K_1") (pintype "passive"))
      (node (ref "U11") (pin "3") (pinfunction "2Y4_3") (pintype "passive"))
    )
    (net (code "66") (name "Net-(LED71-A)") (class "Default")
      (node (ref "LED71") (pin "2") (pinfunction "A_2") (pintype "passive"))
      (node (ref "R308") (pin "2") (pinfunction "2_2") (pintype "passive"))
    )
    (net (code "67") (name "Net-(LED71-K)") (class "Default")
      (node (ref "LED71") (pin "1") (pinfunction "K_1") (pintype "passive"))
      (node (ref "U10") (pin "18") (pinfunction "1Y1_18") (pintype "passive"))
    )
    (net (code "68") (name "Net-(LED72-A)") (class "Default")
      (node (ref "LED72") (pin "2") (pinfunction "A_2") (pintype "passive"))
      (node (ref "R309") (pin "2") (pinfunction "2_2") (pintype "passive"))
    )
    (net (code "69") (name "Net-(LED72-K)") (class "Default")
      (node (ref "LED72") (pin "1") (pinfunction "K_1") (pintype "passive"))
      (node (ref "U10") (pin "16") (pinfunction "1Y2_16") (pintype "passive"))
    )
    (net (code "70") (name "Net-(LED73-A)") (class "Default")
      (node (ref "LED73") (pin "2") (pinfunction "A_2") (pintype "passive"))
      (node (ref "R310") (pin "2") (pinfunction "2_2") (pintype "passive"))
    )
    (net (code "71") (name "Net-(LED73-K)") (class "Default")
      (node (ref "LED73") (pin "1") (pinfunction "K_1") (pintype "passive"))
      (node (ref "U10") (pin "14") (pinfunction "1Y3_14") (pintype "passive"))
    )
    (net (code "72") (name "Net-(LED74-A)") (class "Default")
      (node (ref "LED74") (pin "2") (pinfunction "A_2") (pintype "passive"))
      (node (ref "R311") (pin "2") (pinfunction "2_2") (pintype "passive"))
    )
    (net (code "73") (name "Net-(LED74-K)") (class "Default")
      (node (ref "LED74") (pin "1") (pinfunction "K_1") (pintype "passive"))
      (node (ref "U10") (pin "12") (pinfunction "1Y4_12") (pintype "passive"))
    )
    (net (code "74") (name "Net-(LED75-A)") (class "Default")
      (node (ref "LED75") (pin "2") (pinfunction "A_2") (pintype "passive"))
      (node (ref "R312") (pin "2") (pinfunction "2_2") (pintype "passive"))
    )
    (net (code "75") (name "Net-(LED75-K)") (class "Default")
      (node (ref "LED75") (pin "1") (pinfunction "K_1") (pintype "passive"))
      (node (ref "U10") (pin "9") (pinfunction "2Y1_9") (pintype "passive"))
    )
    (net (code "76") (name "Net-(LED76-A)") (class "Default")
      (node (ref "LED76") (pin "2") (pinfunction "A_2") (pintype "passive"))
      (node (ref "R313") (pin "2") (pinfunction "2_2") (pintype "passive"))
    )
    (net (code "77") (name "Net-(LED76-K)") (class "Default")
      (node (ref "LED76") (pin "1") (pinfunction "K_1") (pintype "passive"))
      (node (ref "U10") (pin "7") (pinfunction "2Y2_7") (pintype "passive"))
    )
    (net (code "78") (name "Net-(LED77-A)") (class "Default")
      (node (ref "LED77") (pin "2") (pinfunction "A_2") (pintype "passive"))
      (node (ref "R314") (pin "2") (pinfunction "2_2") (pintype "passive"))
    )
    (net (code "79") (name "Net-(LED77-K)") (class "Default")
      (node (ref "LED77") (pin "1") (pinfunction "K_1") (pintype "passive"))
      (node (ref "U10") (pin "5") (pinfunction "2Y3_5") (pintype "passive"))
    )
    (net (code "80") (name "Net-(LED78-A)") (class "Default")
      (node (ref "LED78") (pin "2") (pinfunction "A_2") (pintype "passive"))
      (node (ref "R315") (pin "2") (pinfunction "2_2") (pintype "passive"))
    )
    (net (code "81") (name "Net-(LED78-K)") (class "Default")
      (node (ref "LED78") (pin "1") (pinfunction "K_1") (pintype "passive"))
      (node (ref "U10") (pin "3") (pinfunction "2Y4_3") (pintype "passive"))
    )
    (net (code "82") (name "Net-(PC8-A)") (class "Default")
      (node (ref "PC8") (pin "2") (pinfunction "A_2") (pintype "passive"))
      (node (ref "R286") (pin "2") (pinfunction "2_2") (pintype "passive"))
    )
    (net (code "83") (name "Net-(PC8-K)") (class "Default")
      (node (ref "PC8") (pin "1") (pinfunction "K_1") (pintype "passive"))
      (node (ref "R299") (pin "2") (pinfunction "2_2") (pintype "passive"))
    )
    (net (code "84") (name "Net-(PC9-A)") (class "Default")
      (node (ref "PC9") (pin "2") (pinfunction "A_2") (pintype "passive"))
      (node (ref "R285") (pin "2") (pinfunction "2_2") (pintype "passive"))
    )
    (net (code "85") (name "Net-(PC9-K)") (class "Default")
      (node (ref "PC9") (pin "1") (pinfunction "K_1") (pintype "passive"))
      (node (ref "R298") (pin "2") (pinfunction "2_2") (pintype "passive"))
    )
    (net (code "86") (name "Net-(PC10-A)") (class "Default")
      (node (ref "PC10") (pin "2") (pinfunction "A_2") (pintype "passive"))
      (node (ref "R284") (pin "2") (pinfunction "2_2") (pintype "passive"))
    )
    (net (code "87") (name "Net-(PC10-K)") (class "Default")
      (node (ref "PC10") (pin "1") (pinfunction "K_1") (pintype "passive"))
      (node (ref "R297") (pin "2") (pinfunction "2_2") (pintype "passive"))
    )
    (net (code "88") (name "Net-(PC11-A)") (class "Default")
      (node (ref "PC11") (pin "2") (pinfunction "A_2") (pintype "passive"))
      (node (ref "R283") (pin "2") (pinfunction "2_2") (pintype "passive"))
    )
    (net (code "89") (name "Net-(PC11-K)") (class "Default")
      (node (ref "PC11") (pin "1") (pinfunction "K_1") (pintype "passive"))
      (node (ref "R295") (pin "2") (pinfunction "2_2") (pintype "passive"))
    )
  )
)
